# Voltage_Regulator.net
KiCad netlist of a schematic drawn in Altium Designer
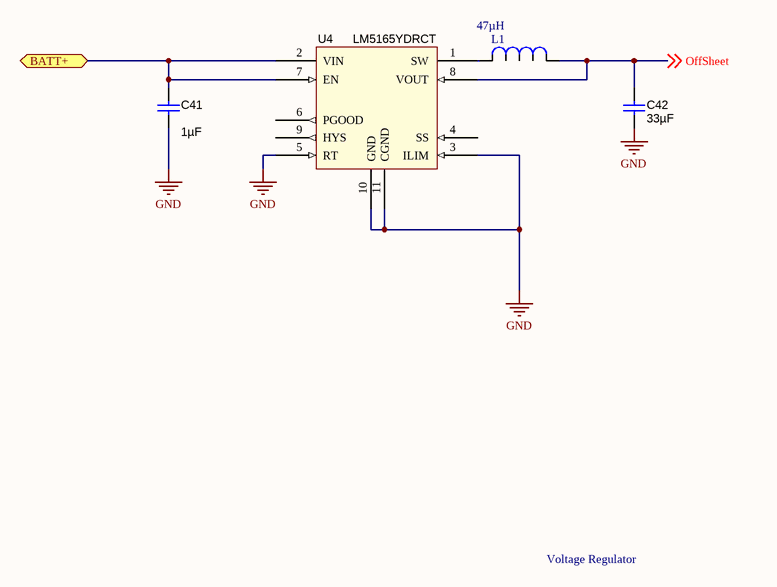
[diagram p0: Voltage Regulator.SchDoc]

(export (version "E")
  (design (tool "Eeschema 10.0.6"))
  (components
    (comp (ref "C41")
      (value "CGA4J3X7S2A105M125AB")
      (footprint "CAP 0805/2012")
      (description "CAP CER 1UF 100V X7S 0805")
      (fields
        (field (name "MANUFACTURER") "TDK Corporation")
        (field (name "VALUEDISPLAYED") "1µF")
        (field (name "PUBLISHER") "Texas Instruments")
      )
      (libsource (lib "TIDA00792E2_AFE") (part "CGA4J3X7S2A105M125AB"))
    )
    (comp (ref "C42")
      (value "C2012X5R0J336M125AC")
      (footprint "CAP 0805/2012")
      (description "CAP CER 33UF 6.3V X5R 0805")
      (fields (field (name "MANUFACTURER") "TDK Corporation") (field (name "VALUEDISPLAYED") "33µF"))
      (libsource (lib "TIDA00792E2_AFE") (part "C2012X5R0J336M125AC"))
    )
    (comp (ref "L1")
      (value "NR4018T470M")
      (footprint "IND NR4018T470M")
      (description "INDUCTOR 47u HENRY 20%")
      (fields (field (name "MANUFACTURER") "Taiyo Yuden") (field (name "VALUEDISPLAYED") "47µH"))
      (libsource (lib "TIDA00792E2_AFE") (part "NR4018T470M"))
    )
    (comp (ref "U4")
      (value "LM5165YDRCT")
      (footprint "SON50P300X100_HS-11N")
      (description "IC REG BUCK 3.3V 0.15A 10VSON")
      (fields
        (field (name "MANUFACTURER") "Texas Instruments")
        (field (name "SYMBOLCREATOR") "x0208325")
        (field (name "PUBLISHER") "Texas Instruments")
      )
      (libsource (lib "TIDA00792E2_AFE") (part "LM5165YDRCT"))
    )
  )
  (nets
    (net (code "1") (name "/BATT+") (class "Default")
      (node (ref "C41") (pin "1") (pinfunction "1_1") (pintype "passive"))
      (node (ref "U4") (pin "2") (pinfunction "VIN_2") (pintype "power_in"))
      (node (ref "U4") (pin "7") (pinfunction "EN_7") (pintype "input"))
    )
    (net (code "2") (name "GND") (class "Default")
      (node (ref "C41") (pin "2") (pinfunction "2_2") (pintype "passive"))
      (node (ref "C42") (pin "2") (pinfunction "2_2") (pintype "passive"))
      (node (ref "U4") (pin "10") (pinfunction "GND_10") (pintype "power_in"))
      (node (ref "U4") (pin "11") (pinfunction "CGND_11") (pintype "power_in"))
      (node (ref "U4") (pin "3") (pinfunction "ILIM_3") (pintype "input"))
      (node (ref "U4") (pin "5") (pinfunction "RT_5") (pintype "input"))
    )
    (net (code "3") (name "Net-(U4-SW)") (class "Default")
      (node (ref "L1") (pin "2") (pinfunction "2_2") (pintype "passive"))
      (node (ref "U4") (pin "1") (pinfunction "SW_1") (pintype "power_in"))
    )
    (net (code "4") (name "OffSheet") (class "Default")
      (node (ref "C42") (pin "1") (pinfunction "1_1") (pintype "passive"))
      (node (ref "L1") (pin "1") (pinfunction "1_1") (pintype "passive"))
      (node (ref "U4") (pin "8") (pinfunction "VOUT_8") (pintype "input"))
    )
    (net (code "5") (name "unconnected-(U4-HYS-Pad9)") (class "Default")
      (node (ref "U4") (pin "9") (pinfunction "HYS_9") (pintype "output"))
    )
    (net (code "6") (name "unconnected-(U4-PGOOD-Pad6)") (class "Default")
      (node (ref "U4") (pin "6") (pinfunction "PGOOD_6") (pintype "output"))
    )
    (net (code "7") (name "unconnected-(U4-SS-Pad4)") (class "Default")
      (node (ref "U4") (pin "4") (pinfunction "SS_4") (pintype "input"))
    )
  )
)
